# ATTiny85.net
KiCad netlist of a schematic drawn in EAGLE
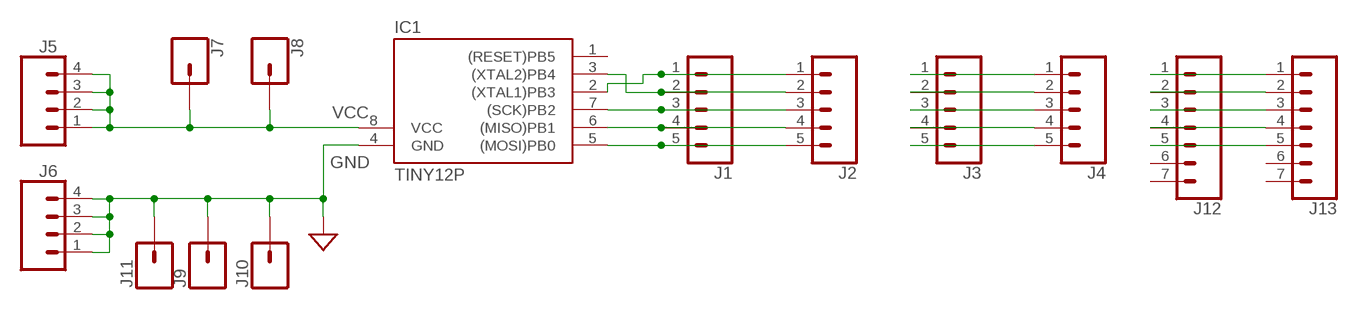
[diagram p0: schematic, sheet 1]

(export (version "E")
  (design (tool "Eeschema 10.0.6"))
  (components
    (comp (ref "IC1")
      (value "TINY12P")
      (footprint "eagle-import:DIL08")
      (libsource (lib "eagle-import") (part "TINY12P"))
    )
    (comp (ref "J1")
      (value "CONN_05NO_SILK")
      (footprint "eagle-import:1X05_NO_SILK")
      (libsource (lib "eagle-import") (part "CONN_05NO_SILK"))
    )
    (comp (ref "J2")
      (value "CONN_05NO_SILK")
      (footprint "eagle-import:1X05_NO_SILK")
      (libsource (lib "eagle-import") (part "CONN_05NO_SILK"))
    )
    (comp (ref "J3")
      (value "CONN_05NO_SILK")
      (footprint "eagle-import:1X05_NO_SILK")
      (libsource (lib "eagle-import") (part "CONN_05NO_SILK"))
    )
    (comp (ref "J4")
      (value "CONN_05NO_SILK")
      (footprint "eagle-import:1X05_NO_SILK")
      (libsource (lib "eagle-import") (part "CONN_05NO_SILK"))
    )
    (comp (ref "J5")
      (value "CONN_041X04_NO_SILK")
      (footprint "eagle-import:1X04_NO_SILK")
      (libsource (lib "eagle-import") (part "CONN_041X04_NO_SILK"))
    )
    (comp (ref "J6")
      (value "CONN_041X04_NO_SILK")
      (footprint "eagle-import:1X04_NO_SILK")
      (libsource (lib "eagle-import") (part "CONN_041X04_NO_SILK"))
    )
    (comp (ref "J7")
      (value "CONN_01PTH_NO_SILK_KIT")
      (footprint "eagle-import:1X01NS_KIT")
      (libsource (lib "eagle-import") (part "CONN_01PTH_NO_SILK_KIT"))
    )
    (comp (ref "J8")
      (value "CONN_01PTH_NO_SILK_KIT")
      (footprint "eagle-import:1X01NS_KIT")
      (libsource (lib "eagle-import") (part "CONN_01PTH_NO_SILK_KIT"))
    )
    (comp (ref "J9")
      (value "CONN_01PTH_NO_SILK_KIT")
      (footprint "eagle-import:1X01NS_KIT")
      (libsource (lib "eagle-import") (part "CONN_01PTH_NO_SILK_KIT"))
    )
    (comp (ref "J10")
      (value "CONN_01PTH_NO_SILK_KIT")
      (footprint "eagle-import:1X01NS_KIT")
      (libsource (lib "eagle-import") (part "CONN_01PTH_NO_SILK_KIT"))
    )
    (comp (ref "J11")
      (value "CONN_01PTH_NO_SILK_KIT")
      (footprint "eagle-import:1X01NS_KIT")
      (libsource (lib "eagle-import") (part "CONN_01PTH_NO_SILK_KIT"))
    )
    (comp (ref "J12")
      (value "CONN_07NO_SILK")
      (footprint "eagle-import:1X07_NO_SILK")
      (libsource (lib "eagle-import") (part "CONN_07NO_SILK"))
    )
    (comp (ref "J13")
      (value "CONN_07NO_SILK")
      (footprint "eagle-import:1X07_NO_SILK")
      (libsource (lib "eagle-import") (part "CONN_07NO_SILK"))
    )
  )
  (nets
    (net (code "1") (name "/VCC") (class "Default")
      (node (ref "IC1") (pin "8") (pinfunction "VCC_8") (pintype "power_in"))
      (node (ref "J5") (pin "1") (pinfunction "1_1") (pintype "passive"))
      (node (ref "J5") (pin "2") (pinfunction "2_2") (pintype "passive"))
      (node (ref "J5") (pin "3") (pinfunction "3_3") (pintype "passive"))
      (node (ref "J5") (pin "4") (pinfunction "4_4") (pintype "passive"))
      (node (ref "J7") (pin "1") (pinfunction "1_1") (pintype "passive"))
      (node (ref "J8") (pin "1") (pinfunction "1_1") (pintype "passive"))
    )
    (net (code "2") (name "GND") (class "Default")
      (node (ref "IC1") (pin "4") (pinfunction "GND_4") (pintype "power_in"))
      (node (ref "J10") (pin "1") (pinfunction "1_1") (pintype "passive"))
      (node (ref "J11") (pin "1") (pinfunction "1_1") (pintype "passive"))
      (node (ref "J6") (pin "1") (pinfunction "1_1") (pintype "passive"))
      (node (ref "J6") (pin "2") (pinfunction "2_2") (pintype "passive"))
      (node (ref "J6") (pin "3") (pinfunction "3_3") (pintype "passive"))
      (node (ref "J6") (pin "4") (pinfunction "4_4") (pintype "passive"))
      (node (ref "J9") (pin "1") (pinfunction "1_1") (pintype "passive"))
    )
    (net (code "3") (name "Net-(IC1-(MISO)PB1)") (class "Default")
      (node (ref "IC1") (pin "6") (pinfunction "(MISO)PB1_6") (pintype "bidirectional"))
      (node (ref "J1") (pin "4") (pinfunction "4_4") (pintype "passive"))
      (node (ref "J2") (pin "4") (pinfunction "4_4") (pintype "passive"))
    )
    (net (code "4") (name "Net-(IC1-(MOSI)PB0)") (class "Default")
      (node (ref "IC1") (pin "5") (pinfunction "(MOSI)PB0_5") (pintype "bidirectional"))
      (node (ref "J1") (pin "5") (pinfunction "5_5") (pintype "passive"))
      (node (ref "J2") (pin "5") (pinfunction "5_5") (pintype "passive"))
    )
    (net (code "5") (name "Net-(IC1-(SCK)PB2)") (class "Default")
      (node (ref "IC1") (pin "7") (pinfunction "(SCK)PB2_7") (pintype "bidirectional"))
      (node (ref "J1") (pin "3") (pinfunction "3_3") (pintype "passive"))
      (node (ref "J2") (pin "3") (pinfunction "3_3") (pintype "passive"))
    )
    (net (code "6") (name "Net-(IC1-(XTAL1)PB3)") (class "Default")
      (node (ref "IC1") (pin "2") (pinfunction "(XTAL1)PB3_2") (pintype "bidirectional"))
      (node (ref "J1") (pin "1") (pinfunction "1_1") (pintype "passive"))
      (node (ref "J2") (pin "1") (pinfunction "1_1") (pintype "passive"))
    )
    (net (code "7") (name "Net-(IC1-(XTAL2)PB4)") (class "Default")
      (node (ref "IC1") (pin "3") (pinfunction "(XTAL2)PB4_3") (pintype "bidirectional"))
      (node (ref "J1") (pin "2") (pinfunction "2_2") (pintype "passive"))
      (node (ref "J2") (pin "2") (pinfunction "2_2") (pintype "passive"))
    )
    (net (code "8") (name "Net-(J3-Pad1)") (class "Default")
      (node (ref "J3") (pin "1") (pinfunction "1_1") (pintype "passive"))
      (node (ref "J4") (pin "1") (pinfunction "1_1") (pintype "passive"))
    )
    (net (code "9") (name "Net-(J3-Pad2)") (class "Default")
      (node (ref "J3") (pin "2") (pinfunction "2_2") (pintype "passive"))
      (node (ref "J4") (pin "2") (pinfunction "2_2") (pintype "passive"))
    )
    (net (code "10") (name "Net-(J3-Pad3)") (class "Default")
      (node (ref "J3") (pin "3") (pinfunction "3_3") (pintype "passive"))
      (node (ref "J4") (pin "3") (pinfunction "3_3") (pintype "passive"))
    )
    (net (code "11") (name "Net-(J3-Pad4)") (class "Default")
      (node (ref "J3") (pin "4") (pinfunction "4_4") (pintype "passive"))
      (node (ref "J4") (pin "4") (pinfunction "4_4") (pintype "passive"))
    )
    (net (code "12") (name "Net-(J3-Pad5)") (class "Default")
      (node (ref "J3") (pin "5") (pinfunction "5_5") (pintype "passive"))
      (node (ref "J4") (pin "5") (pinfunction "5_5") (pintype "passive"))
    )
    (net (code "13") (name "Net-(J12-Pad1)") (class "Default")
      (node (ref "J12") (pin "1") (pinfunction "1_1") (pintype "passive"))
      (node (ref "J13") (pin "1") (pinfunction "1_1") (pintype "passive"))
    )
    (net (code "14") (name "Net-(J12-Pad2)") (class "Default")
      (node (ref "J12") (pin "2") (pinfunction "2_2") (pintype "passive"))
      (node (ref "J13") (pin "2") (pinfunction "2_2") (pintype "passive"))
    )
    (net (code "15") (name "Net-(J12-Pad3)") (class "Default")
      (node (ref "J12") (pin "3") (pinfunction "3_3") (pintype "passive"))
      (node (ref "J13") (pin "3") (pinfunction "3_3") (pintype "passive"))
    )
    (net (code "16") (name "Net-(J12-Pad4)") (class "Default")
      (node (ref "J12") (pin "4") (pinfunction "4_4") (pintype "passive"))
      (node (ref "J13") (pin "4") (pinfunction "4_4") (pintype "passive"))
    )
    (net (code "17") (name "Net-(J12-Pad5)") (class "Default")
      (node (ref "J12") (pin "5") (pinfunction "5_5") (pintype "passive"))
      (node (ref "J13") (pin "5") (pinfunction "5_5") (pintype "passive"))
    )
    (net (code "18") (name "unconnected-(IC1-(RESET)PB5-Pad1)") (class "Default")
      (node (ref "IC1") (pin "1") (pinfunction "(RESET)PB5_1") (pintype "bidirectional"))
    )
    (net (code "19") (name "unconnected-(J12-Pad6)") (class "Default")
      (node (ref "J12") (pin "6") (pinfunction "6_6") (pintype "passive"))
    )
    (net (code "20") (name "unconnected-(J12-Pad7)") (class "Default")
      (node (ref "J12") (pin "7") (pinfunction "7_7") (pintype "passive"))
    )
    (net (code "21") (name "unconnected-(J13-Pad6)") (class "Default")
      (node (ref "J13") (pin "6") (pinfunction "6_6") (pintype "passive"))
    )
    (net (code "22") (name "unconnected-(J13-Pad7)") (class "Default")
      (node (ref "J13") (pin "7") (pinfunction "7_7") (pintype "passive"))
    )
  )
)
